# Power_12V-0_5A.net
KiCad netlist of a schematic drawn in EAGLE
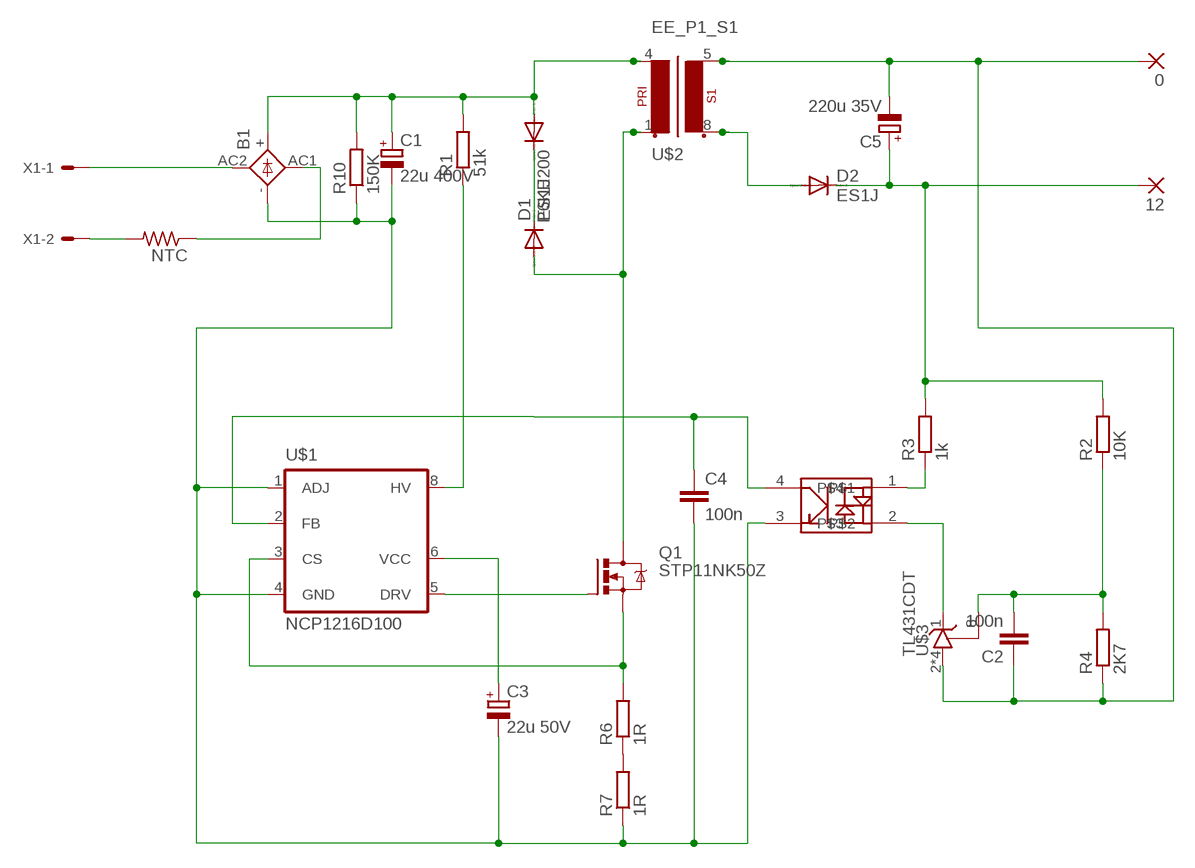
[diagram p0: schematic, sheet 1]

(export (version "E")
  (design (tool "Eeschema 10.0.6"))
  (components
    (comp (ref "0")
      (value "2,54/0,8")
      (footprint "eagle-import:2,54_0,8")
      (libsource (lib "eagle-import") (part "2,54/0,8"))
    )
    (comp (ref "12")
      (value "2,54/0,8")
      (footprint "eagle-import:2,54_0,8")
      (libsource (lib "eagle-import") (part "2,54/0,8"))
    )
    (comp (ref "B1")
      (value "KBL")
      (footprint "eagle-import:KBL")
      (libsource (lib "eagle-import") (part "KBL"))
    )
    (comp (ref "C1")
      (value "22u 400V")
      (footprint "eagle-import:E5-13")
      (libsource (lib "eagle-import") (part "CPOL-EUE5-13"))
    )
    (comp (ref "C2")
      (value "100n")
      (footprint "eagle-import:C1206")
      (libsource (lib "eagle-import") (part "C-EUC1206"))
    )
    (comp (ref "C3")
      (value "22u 50V")
      (footprint "eagle-import:E2,5-5")
      (libsource (lib "eagle-import") (part "CPOL-EUE2.5-5"))
    )
    (comp (ref "C4")
      (value "100n")
      (footprint "eagle-import:C1206")
      (libsource (lib "eagle-import") (part "C-EUC1206"))
    )
    (comp (ref "C5")
      (value "220u 35V")
      (footprint "eagle-import:E2,5-7")
      (libsource (lib "eagle-import") (part "CPOL-EUE2.5-7"))
    )
    (comp (ref "D1")
      (value "ES1J")
      (footprint "eagle-import:DO-214AC")
      (libsource (lib "eagle-import") (part "DIODE-DO-214AC"))
    )
    (comp (ref "D2")
      (value "ES1J")
      (footprint "eagle-import:DO-214AC")
      (libsource (lib "eagle-import") (part "DIODE-DO-214AC"))
    )
    (comp (ref "NTC")
      (value "R-US_0207/10")
      (footprint "eagle-import:0207_10")
      (libsource (lib "eagle-import") (part "R-US_0207/10"))
    )
    (comp (ref "P6KE200")
      (value "DIODE-SMB")
      (footprint "eagle-import:SMB")
      (libsource (lib "eagle-import") (part "DIODE-SMB"))
    )
    (comp (ref "Q1")
      (value "STP11NK50Z")
      (footprint "eagle-import:TO220BV")
      (libsource (lib "eagle-import") (part "IRF740"))
    )
    (comp (ref "R1")
      (value "51k")
      (footprint "eagle-import:0922_22")
      (libsource (lib "eagle-import") (part "R-EU_0922/22"))
    )
    (comp (ref "R2")
      (value "10K")
      (footprint "eagle-import:R1206")
      (libsource (lib "eagle-import") (part "R-EU_R1206"))
    )
    (comp (ref "R3")
      (value "1k")
      (footprint "eagle-import:R1206")
      (libsource (lib "eagle-import") (part "R-EU_R1206"))
    )
    (comp (ref "R4")
      (value "2K7")
      (footprint "eagle-import:R1206")
      (libsource (lib "eagle-import") (part "R-EU_R1206"))
    )
    (comp (ref "R6")
      (value "1R")
      (footprint "eagle-import:R1206")
      (libsource (lib "eagle-import") (part "R-EU_R1206"))
    )
    (comp (ref "R7")
      (value "1R")
      (footprint "eagle-import:R1206")
      (libsource (lib "eagle-import") (part "R-EU_R1206"))
    )
    (comp (ref "R10")
      (value "150K")
      (footprint "eagle-import:0204_7")
      (libsource (lib "eagle-import") (part "R-EU_0204/7"))
    )
    (comp (ref "U$1")
      (value "NCP1216D100")
      (footprint "eagle-import:SOP8")
      (libsource (lib "eagle-import") (part "NCP1200-100SO"))
    )
    (comp (ref "U$2")
      (value "EE_P1_S1")
      (footprint "eagle-import:EE25_P1_S1")
      (libsource (lib "eagle-import") (part "EE_P1_S1"))
    )
    (comp (ref "U$3")
      (value "TL431CDT")
      (footprint "eagle-import:SO8")
      (libsource (lib "eagle-import") (part "TL431CDT"))
    )
    (comp (ref "U$5")
      (value "EL3H4(TA)-VG")
      (footprint "eagle-import:SSOP4")
      (libsource (lib "eagle-import") (part "EL3H4(TA)-VG"))
    )
    (comp (ref "X1")
      (value "KK-156-2")
      (footprint "eagle-import:KK-156-2")
      (libsource (lib "eagle-import") (part "KK-156-2"))
    )
  )
  (nets
    (net (code "1") (name "Net-(0-P)") (class "Default")
      (node (ref "0") (pin "1") (pinfunction "P_1") (pintype "passive"))
      (node (ref "C2") (pin "1") (pinfunction "1_1") (pintype "passive"))
      (node (ref "C5") (pin "-") (pinfunction "-_-") (pintype "passive"))
      (node (ref "R4") (pin "1") (pinfunction "1_1") (pintype "passive"))
      (node (ref "U$2") (pin "5") (pinfunction "S1-2_5") (pintype "passive"))
      (node (ref "U$3") (pin "2") (pinfunction "A_2") (pintype "passive"))
      (node (ref "U$3") (pin "3") (pinfunction "A_3") (pintype "passive"))
      (node (ref "U$3") (pin "6") (pinfunction "A_6") (pintype "passive"))
      (node (ref "U$3") (pin "7") (pinfunction "A_7") (pintype "passive"))
    )
    (net (code "2") (name "Net-(12-P)") (class "Default")
      (node (ref "12") (pin "1") (pinfunction "P_1") (pintype "passive"))
      (node (ref "C5") (pin "+") (pinfunction "+_+") (pintype "passive"))
      (node (ref "D2") (pin "C") (pinfunction "C_C") (pintype "passive"))
      (node (ref "R2") (pin "2") (pinfunction "2_2") (pintype "passive"))
      (node (ref "R3") (pin "2") (pinfunction "2_2") (pintype "passive"))
    )
    (net (code "3") (name "Net-(B1-AC1)") (class "Default")
      (node (ref "B1") (pin "AC2") (pinfunction "AC1_AC2") (pintype "passive"))
      (node (ref "X1") (pin "1") (pinfunction "S_1") (pintype "passive"))
    )
    (net (code "4") (name "Net-(B1-AC2)") (class "Default")
      (node (ref "B1") (pin "AC1") (pinfunction "AC2_AC1") (pintype "passive"))
      (node (ref "NTC") (pin "1") (pinfunction "1_1") (pintype "passive"))
    )
    (net (code "5") (name "Net-(D1-PadC)") (class "Default")
      (node (ref "D1") (pin "C") (pinfunction "C_C") (pintype "passive"))
      (node (ref "P6KE200") (pin "C") (pinfunction "C_C") (pintype "passive"))
    )
    (net (code "6") (name "Net-(R6-Pad1)") (class "Default")
      (node (ref "R6") (pin "1") (pinfunction "1_1") (pintype "passive"))
      (node (ref "R7") (pin "2") (pinfunction "2_2") (pintype "passive"))
    )
    (net (code "7") (name "Net-(U$1-ADJ)") (class "Default")
      (node (ref "B1") (pin "-") (pinfunction "-_-") (pintype "passive"))
      (node (ref "C1") (pin "-") (pinfunction "-_-") (pintype "passive"))
      (node (ref "C3") (pin "-") (pinfunction "-_-") (pintype "passive"))
      (node (ref "C4") (pin "2") (pinfunction "2_2") (pintype "passive"))
      (node (ref "R10") (pin "1") (pinfunction "1_1") (pintype "passive"))
      (node (ref "R7") (pin "1") (pinfunction "1_1") (pintype "passive"))
      (node (ref "U$1") (pin "1") (pinfunction "ADJ_1") (pintype "passive"))
      (node (ref "U$1") (pin "4") (pinfunction "GND_4") (pintype "passive"))
      (node (ref "U$5") (pin "3") (pinfunction "P$3_3") (pintype "bidirectional"))
    )
    (net (code "8") (name "Net-(U$1-CS)") (class "Default")
      (node (ref "Q1") (pin "S") (pinfunction "S_S") (pintype "passive"))
      (node (ref "R6") (pin "2") (pinfunction "2_2") (pintype "passive"))
      (node (ref "U$1") (pin "3") (pinfunction "CS_3") (pintype "input"))
    )
    (net (code "9") (name "Net-(U$1-DRV)") (class "Default")
      (node (ref "Q1") (pin "G") (pinfunction "G_G") (pintype "passive"))
      (node (ref "U$1") (pin "5") (pinfunction "DRV_5") (pintype "power_in"))
    )
    (net (code "10") (name "Net-(U$1-FB)") (class "Default")
      (node (ref "C4") (pin "1") (pinfunction "1_1") (pintype "passive"))
      (node (ref "U$1") (pin "2") (pinfunction "FB_2") (pintype "input"))
      (node (ref "U$5") (pin "4") (pinfunction "P$4_4") (pintype "bidirectional"))
    )
    (net (code "11") (name "Net-(U$1-HV)") (class "Default")
      (node (ref "R1") (pin "1") (pinfunction "1_1") (pintype "passive"))
      (node (ref "U$1") (pin "8") (pinfunction "HV_8") (pintype "passive"))
    )
    (net (code "12") (name "Net-(U$1-VCC)") (class "Default")
      (node (ref "C3") (pin "+") (pinfunction "+_+") (pintype "passive"))
      (node (ref "U$1") (pin "6") (pinfunction "VCC_6") (pintype "output"))
    )
    (net (code "13") (name "Net-(U$2-P1-1)") (class "Default")
      (node (ref "D1") (pin "A") (pinfunction "A_A") (pintype "passive"))
      (node (ref "Q1") (pin "D") (pinfunction "D_D") (pintype "passive"))
      (node (ref "U$2") (pin "1") (pinfunction "P1-1_1") (pintype "passive"))
    )
    (net (code "14") (name "Net-(U$2-P1-2)") (class "Default")
      (node (ref "B1") (pin "+") (pinfunction "+_+") (pintype "passive"))
      (node (ref "C1") (pin "+") (pinfunction "+_+") (pintype "passive"))
      (node (ref "P6KE200") (pin "A") (pinfunction "A_A") (pintype "passive"))
      (node (ref "R1") (pin "2") (pinfunction "2_2") (pintype "passive"))
      (node (ref "R10") (pin "2") (pinfunction "2_2") (pintype "passive"))
      (node (ref "U$2") (pin "4") (pinfunction "P1-2_4") (pintype "passive"))
    )
    (net (code "15") (name "Net-(U$2-S1-1)") (class "Default")
      (node (ref "D2") (pin "A") (pinfunction "A_A") (pintype "passive"))
      (node (ref "U$2") (pin "8") (pinfunction "S1-1_8") (pintype "passive"))
    )
    (net (code "16") (name "Net-(U$3-C)") (class "Default")
      (node (ref "U$3") (pin "1") (pinfunction "C_1") (pintype "passive"))
      (node (ref "U$5") (pin "2") (pinfunction "P$2_2") (pintype "bidirectional"))
    )
    (net (code "17") (name "Net-(U$3-R)") (class "Default")
      (node (ref "C2") (pin "2") (pinfunction "2_2") (pintype "passive"))
      (node (ref "R2") (pin "1") (pinfunction "1_1") (pintype "passive"))
      (node (ref "R4") (pin "2") (pinfunction "2_2") (pintype "passive"))
      (node (ref "U$3") (pin "8") (pinfunction "R_8") (pintype "passive"))
    )
    (net (code "18") (name "Net-(U$5-P$1)") (class "Default")
      (node (ref "R3") (pin "1") (pinfunction "1_1") (pintype "passive"))
      (node (ref "U$5") (pin "1") (pinfunction "P$1_1") (pintype "bidirectional"))
    )
    (net (code "19") (name "Net-(X1B-S)") (class "Default")
      (node (ref "NTC") (pin "2") (pinfunction "2_2") (pintype "passive"))
      (node (ref "X1") (pin "2") (pinfunction "S_2") (pintype "passive"))
    )
  )
)
